# cnc-cape.net
KiCad netlist of a schematic drawn in EAGLE
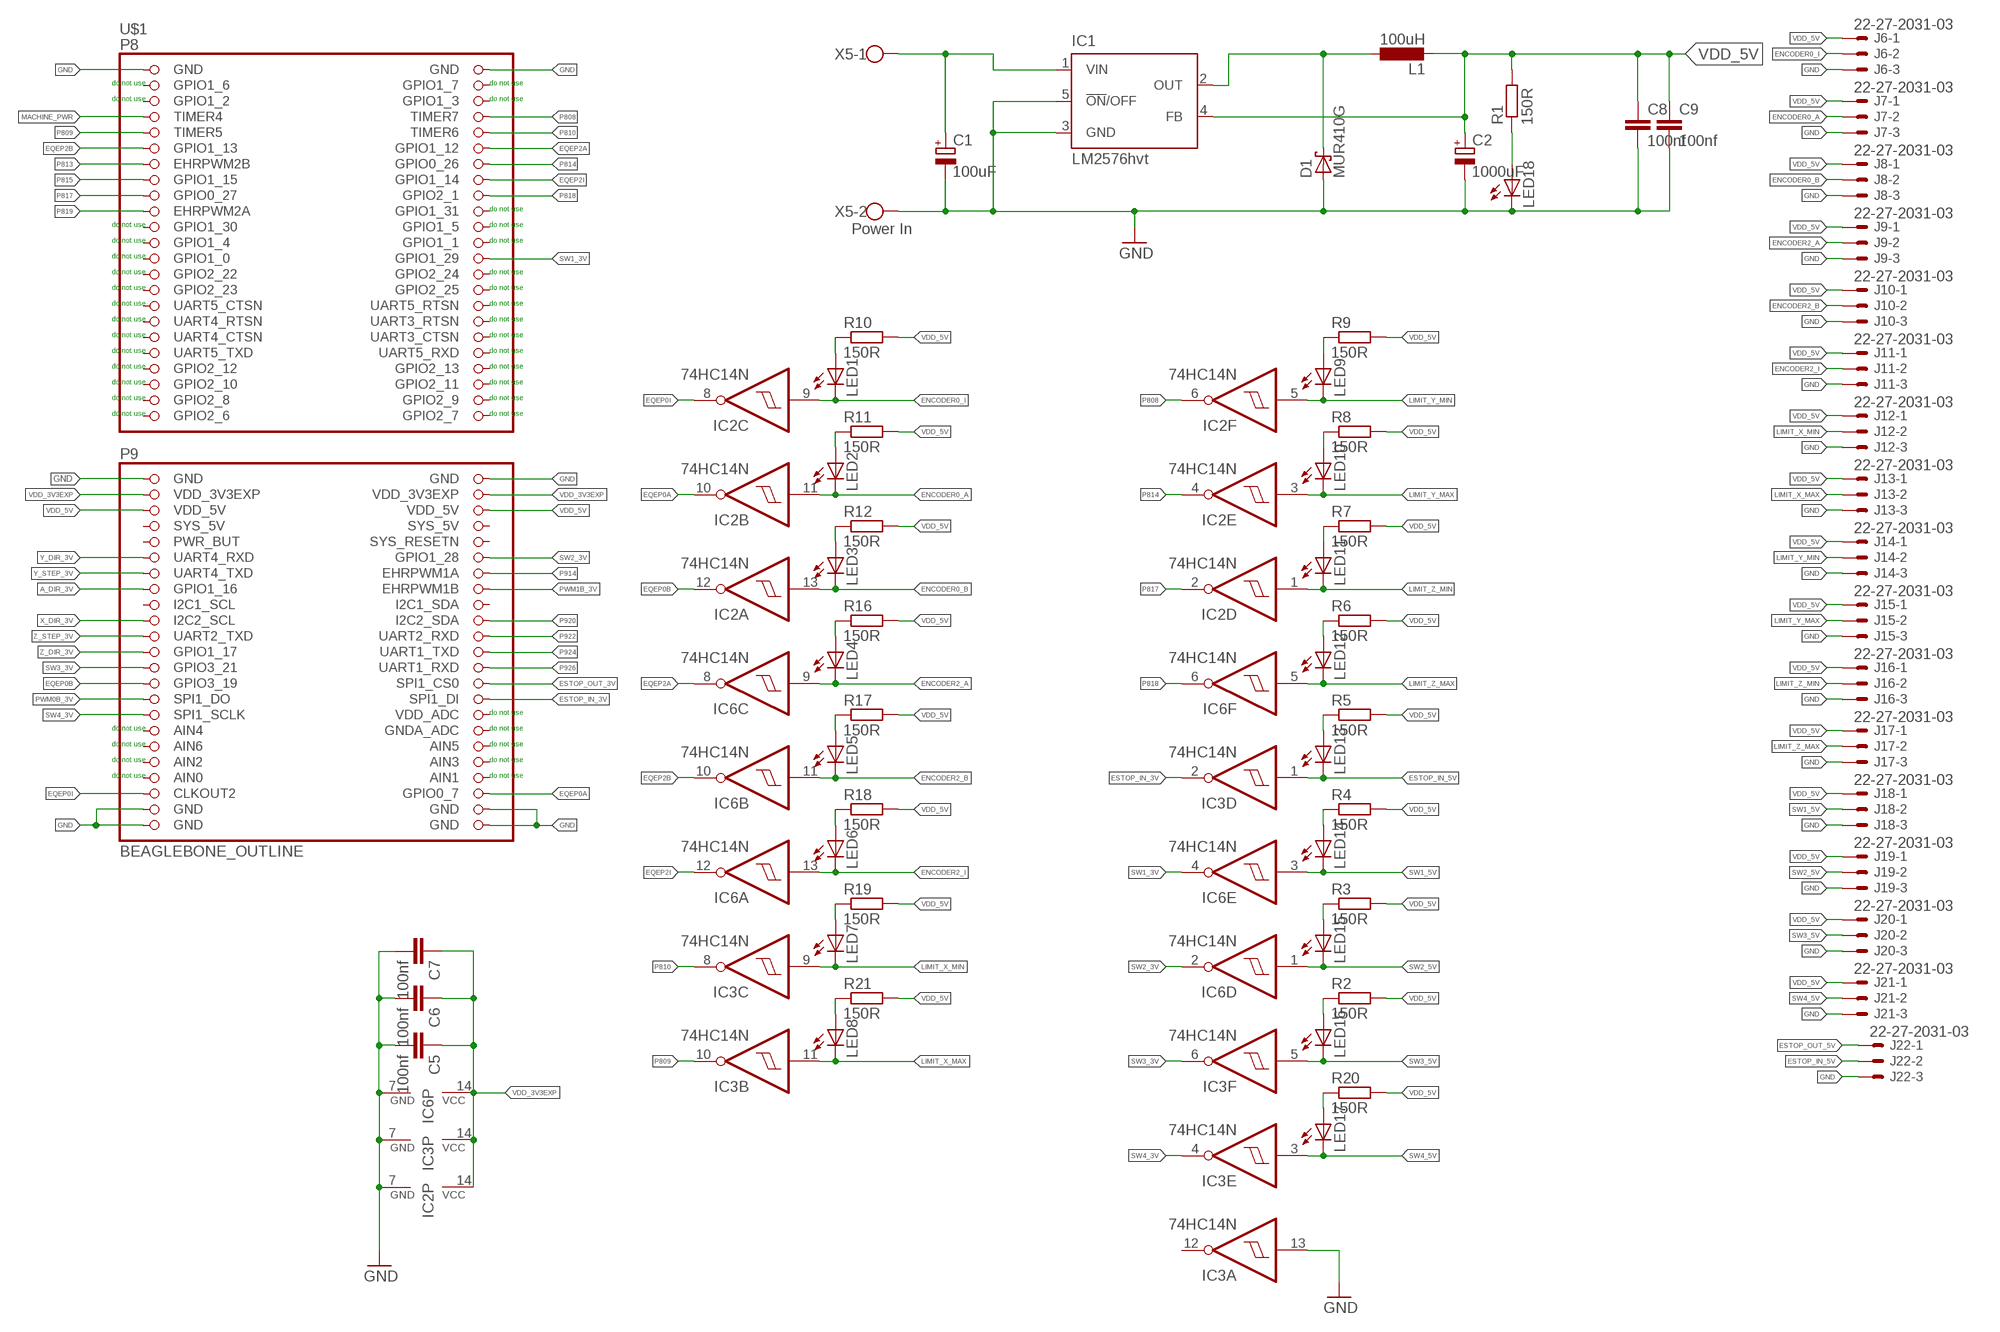
[diagram p0: schematic, sheet 1]
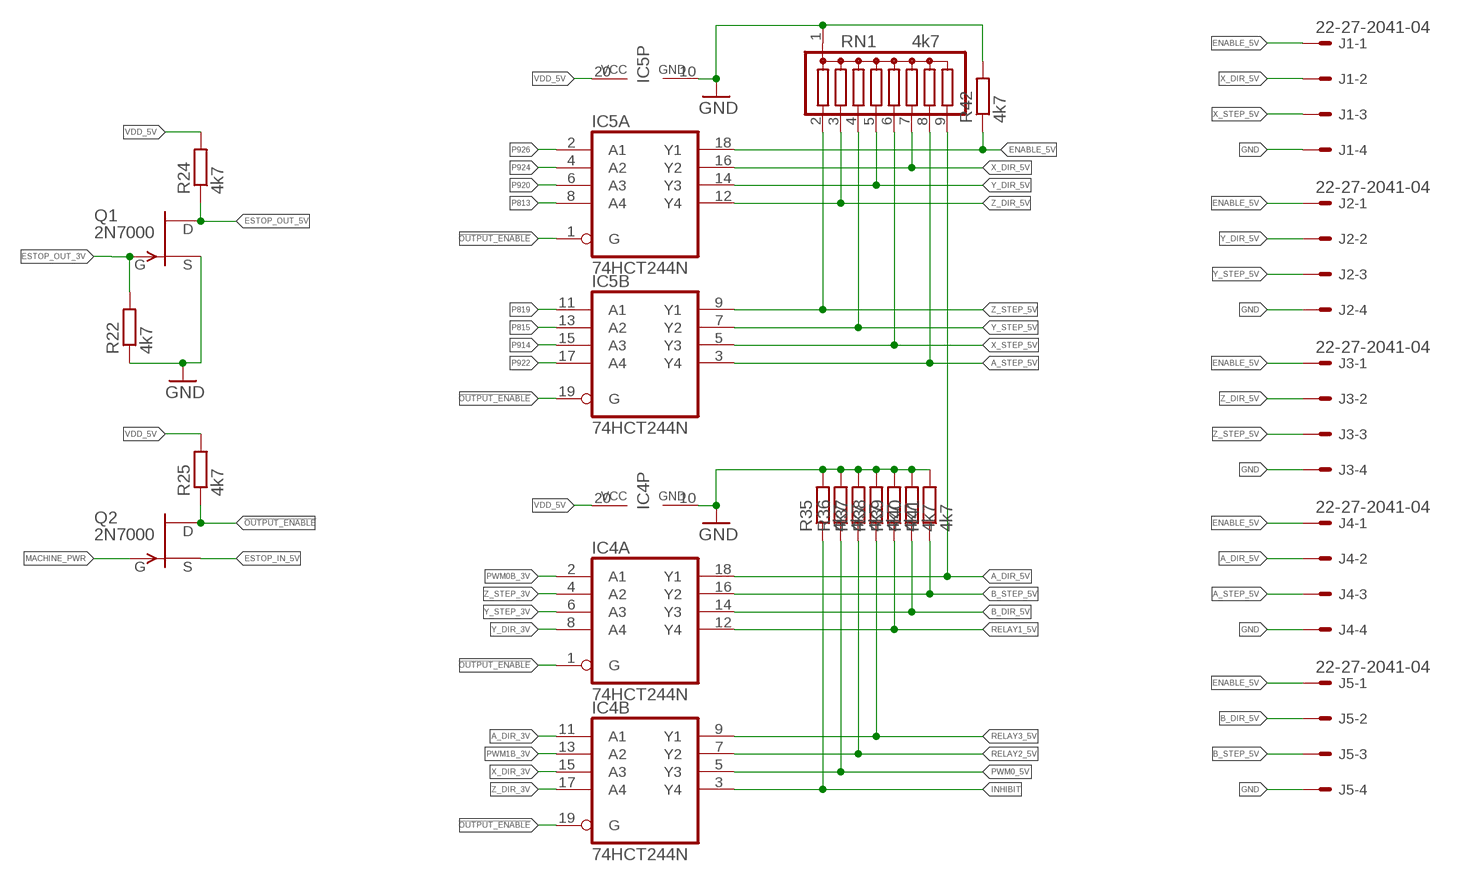
[diagram p1: schematic, sheet 2]
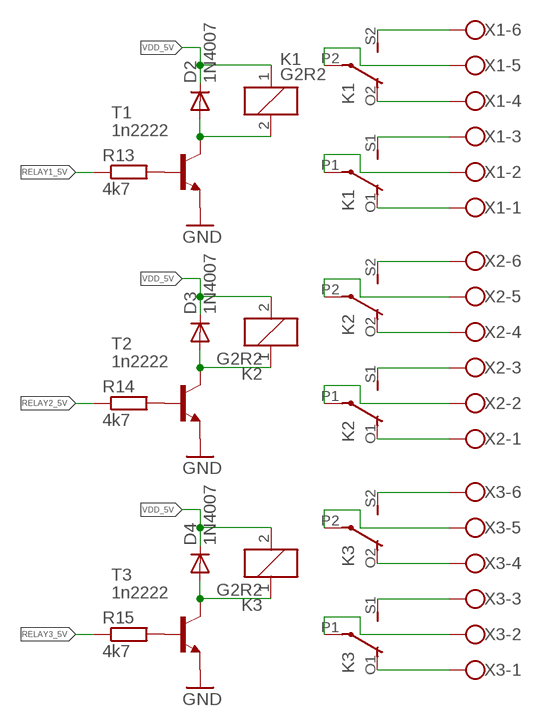
[diagram p2: schematic, sheet 3]
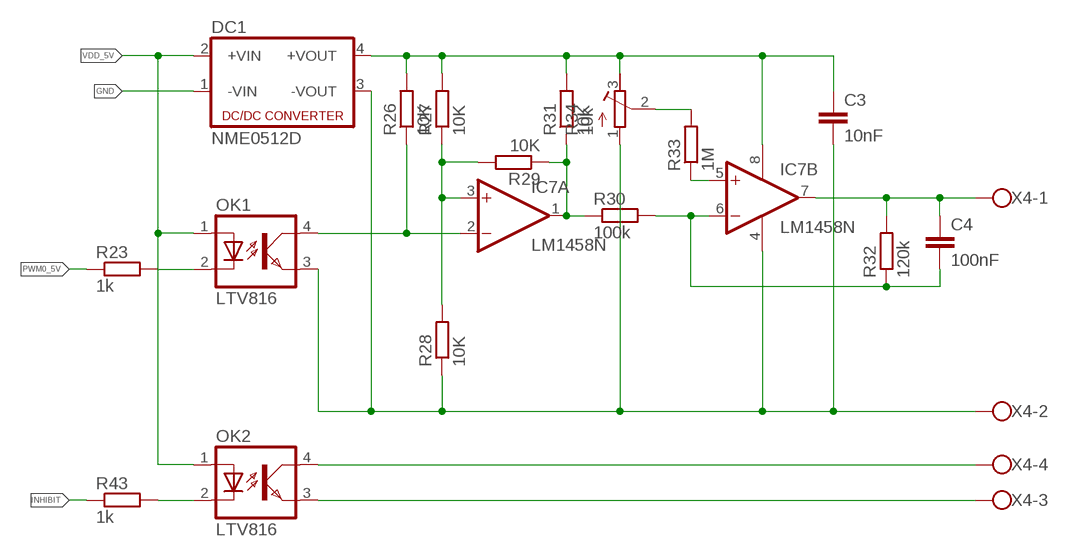
[diagram p3: schematic, sheet 4]

(export (version "E")
  (design (tool "Eeschema 10.0.6"))
  (components
    (comp (ref "IC4")
      (value "74HCT244N")
      (footprint "eagle-import:DIL20")
      (fields (field (name "FARNELL") "382267"))
      (libsource (lib "eagle-import") (part "74244NHCT"))
    )
    (comp (ref "IC5")
      (value "74HCT244N")
      (footprint "eagle-import:DIL20")
      (fields (field (name "FARNELL") "382267"))
      (libsource (lib "eagle-import") (part "74244NHCT"))
    )
    (comp (ref "J1")
      (value "22-27-2041-04")
      (footprint "eagle-import:6410-04")
      (fields (field (name "FARNELL") "9731164"))
      (libsource (lib "eagle-import") (part "22-?-0427-2041"))
    )
    (comp (ref "J2")
      (value "22-27-2041-04")
      (footprint "eagle-import:6410-04")
      (fields (field (name "FARNELL") "9731164"))
      (libsource (lib "eagle-import") (part "22-?-0427-2041"))
    )
    (comp (ref "J3")
      (value "22-27-2041-04")
      (footprint "eagle-import:6410-04")
      (fields (field (name "FARNELL") "9731164"))
      (libsource (lib "eagle-import") (part "22-?-0427-2041"))
    )
    (comp (ref "J4")
      (value "22-27-2041-04")
      (footprint "eagle-import:6410-04")
      (fields (field (name "FARNELL") "9731164"))
      (libsource (lib "eagle-import") (part "22-?-0427-2041"))
    )
    (comp (ref "J5")
      (value "22-27-2041-04")
      (footprint "eagle-import:6410-04")
      (fields (field (name "FARNELL") "9731164"))
      (libsource (lib "eagle-import") (part "22-?-0427-2041"))
    )
    (comp (ref "Q1")
      (value "2N7000")
      (footprint "eagle-import:TO92")
      (libsource (lib "eagle-import") (part "2N3819"))
    )
    (comp (ref "Q2")
      (value "2N7000")
      (footprint "eagle-import:TO92")
      (libsource (lib "eagle-import") (part "2N3819"))
    )
    (comp (ref "R22")
      (value "4k7")
      (footprint "eagle-import:0204_5")
      (libsource (lib "eagle-import") (part "R-EU_0204/5"))
    )
    (comp (ref "R24")
      (value "4k7")
      (footprint "eagle-import:0204_5")
      (libsource (lib "eagle-import") (part "R-EU_0204/5"))
    )
    (comp (ref "R25")
      (value "4k7")
      (footprint "eagle-import:0204_5")
      (libsource (lib "eagle-import") (part "R-EU_0204/5"))
    )
    (comp (ref "R35")
      (value "4k7")
      (footprint "eagle-import:0204_5")
      (libsource (lib "eagle-import") (part "R-EU_0204/5"))
    )
    (comp (ref "R36")
      (value "4k7")
      (footprint "eagle-import:0204_5")
      (libsource (lib "eagle-import") (part "R-EU_0204/5"))
    )
    (comp (ref "R37")
      (value "4k7")
      (footprint "eagle-import:0204_5")
      (libsource (lib "eagle-import") (part "R-EU_0204/5"))
    )
    (comp (ref "R38")
      (value "4k7")
      (footprint "eagle-import:0204_5")
      (libsource (lib "eagle-import") (part "R-EU_0204/5"))
    )
    (comp (ref "R39")
      (value "4k7")
      (footprint "eagle-import:0204_5")
      (libsource (lib "eagle-import") (part "R-EU_0204/5"))
    )
    (comp (ref "R40")
      (value "4k7")
      (footprint "eagle-import:0204_5")
      (libsource (lib "eagle-import") (part "R-EU_0204/5"))
    )
    (comp (ref "R41")
      (value "4k7")
      (footprint "eagle-import:0204_5")
      (libsource (lib "eagle-import") (part "R-EU_0204/5"))
    )
    (comp (ref "R42")
      (value "4k7")
      (footprint "eagle-import:0204_5")
      (libsource (lib "eagle-import") (part "R-EU_0204/5"))
    )
    (comp (ref "RN1")
      (value "4k7")
      (footprint "eagle-import:SIL9")
      (libsource (lib "eagle-import") (part "G08R"))
    )
    (comp (ref "C1")
      (value "100uF")
      (footprint "eagle-import:E5-10,5")
      (libsource (lib "eagle-import") (part "CPOL-EUE5-10.5"))
    )
    (comp (ref "C2")
      (value "1000uF")
      (footprint "eagle-import:E5-10,5")
      (libsource (lib "eagle-import") (part "CPOL-EUE5-10.5"))
    )
    (comp (ref "C5")
      (value "100nf")
      (footprint "eagle-import:C050-024X044")
      (libsource (lib "eagle-import") (part "C-EU050-024X044"))
    )
    (comp (ref "C6")
      (value "100nf")
      (footprint "eagle-import:C050-024X044")
      (libsource (lib "eagle-import") (part "C-EU050-024X044"))
    )
    (comp (ref "C7")
      (value "100nf")
      (footprint "eagle-import:C050-024X044")
      (libsource (lib "eagle-import") (part "C-EU050-024X044"))
    )
    (comp (ref "C8")
      (value "100nf")
      (footprint "eagle-import:C050-024X044")
      (libsource (lib "eagle-import") (part "C-EU050-024X044"))
    )
    (comp (ref "C9")
      (value "100nf")
      (footprint "eagle-import:C050-024X044")
      (libsource (lib "eagle-import") (part "C-EU050-024X044"))
    )
    (comp (ref "D1")
      (value "MUR410G")
      (footprint "eagle-import:DO201T15")
      (libsource (lib "eagle-import") (part "SCHOTTKY-DIODEDO201T15"))
    )
    (comp (ref "IC1")
      (value "LM2576hvt")
      (footprint "eagle-import:T05D")
      (fields (field (name "MPN") "LM2596T-ADJ/LF02"))
      (libsource (lib "eagle-import") (part "LM2596T"))
    )
    (comp (ref "IC2")
      (value "74HC14N")
      (footprint "eagle-import:DIL14")
      (fields (field (name "FARNELL") "1739974"))
      (libsource (lib "eagle-import") (part "7414NHC"))
    )
    (comp (ref "IC3")
      (value "74HC14N")
      (footprint "eagle-import:DIL14")
      (fields (field (name "FARNELL") "1739974"))
      (libsource (lib "eagle-import") (part "7414NHC"))
    )
    (comp (ref "IC6")
      (value "74HC14N")
      (footprint "eagle-import:DIL14")
      (fields (field (name "FARNELL") "1739974"))
      (libsource (lib "eagle-import") (part "7414NHC"))
    )
    (comp (ref "J6")
      (value "22-27-2031-03")
      (footprint "eagle-import:6410-03")
      (fields (field (name "FARNELL") "9731156"))
      (libsource (lib "eagle-import") (part "22-?-0327-2031"))
    )
    (comp (ref "J7")
      (value "22-27-2031-03")
      (footprint "eagle-import:6410-03")
      (fields (field (name "FARNELL") "9731156"))
      (libsource (lib "eagle-import") (part "22-?-0327-2031"))
    )
    (comp (ref "J8")
      (value "22-27-2031-03")
      (footprint "eagle-import:6410-03")
      (fields (field (name "FARNELL") "9731156"))
      (libsource (lib "eagle-import") (part "22-?-0327-2031"))
    )
    (comp (ref "J9")
      (value "22-27-2031-03")
      (footprint "eagle-import:6410-03")
      (libsource (lib "eagle-import") (part "22-?-0327-2031"))
    )
    (comp (ref "J10")
      (value "22-27-2031-03")
      (footprint "eagle-import:6410-03")
      (fields (field (name "FARNELL") "9731156"))
      (libsource (lib "eagle-import") (part "22-?-0327-2031"))
    )
    (comp (ref "J11")
      (value "22-27-2031-03")
      (footprint "eagle-import:6410-03")
      (fields (field (name "FARNELL") "9731156"))
      (libsource (lib "eagle-import") (part "22-?-0327-2031"))
    )
    (comp (ref "J12")
      (value "22-27-2031-03")
      (footprint "eagle-import:6410-03")
      (fields (field (name "FARNELL") "9731156"))
      (libsource (lib "eagle-import") (part "22-?-0327-2031"))
    )
    (comp (ref "J13")
      (value "22-27-2031-03")
      (footprint "eagle-import:6410-03")
      (fields (field (name "FARNELL") "9731156"))
      (libsource (lib "eagle-import") (part "22-?-0327-2031"))
    )
    (comp (ref "J14")
      (value "22-27-2031-03")
      (footprint "eagle-import:6410-03")
      (fields (field (name "FARNELL") "9731156"))
      (libsource (lib "eagle-import") (part "22-?-0327-2031"))
    )
    (comp (ref "J15")
      (value "22-27-2031-03")
      (footprint "eagle-import:6410-03")
      (fields (field (name "FARNELL") "9731156"))
      (libsource (lib "eagle-import") (part "22-?-0327-2031"))
    )
    (comp (ref "J16")
      (value "22-27-2031-03")
      (footprint "eagle-import:6410-03")
      (fields (field (name "FARNELL") "9731156"))
      (libsource (lib "eagle-import") (part "22-?-0327-2031"))
    )
    (comp (ref "J17")
      (value "22-27-2031-03")
      (footprint "eagle-import:6410-03")
      (fields (field (name "FARNELL") "9731156"))
      (libsource (lib "eagle-import") (part "22-?-0327-2031"))
    )
    (comp (ref "J18")
      (value "22-27-2031-03")
      (footprint "eagle-import:6410-03")
      (fields (field (name "FARNELL") "9731156"))
      (libsource (lib "eagle-import") (part "22-?-0327-2031"))
    )
    (comp (ref "J19")
      (value "22-27-2031-03")
      (footprint "eagle-import:6410-03")
      (fields (field (name "FARNELL") "9731156"))
      (libsource (lib "eagle-import") (part "22-?-0327-2031"))
    )
    (comp (ref "J20")
      (value "22-27-2031-03")
      (footprint "eagle-import:6410-03")
      (fields (field (name "FARNELL") "9731156"))
      (libsource (lib "eagle-import") (part "22-?-0327-2031"))
    )
    (comp (ref "J21")
      (value "22-27-2031-03")
      (footprint "eagle-import:6410-03")
      (fields (field (name "FARNELL") "9731156"))
      (libsource (lib "eagle-import") (part "22-?-0327-2031"))
    )
    (comp (ref "J22")
      (value "22-27-2031-03")
      (footprint "eagle-import:6410-03")
      (libsource (lib "eagle-import") (part "22-?-0327-2031"))
    )
    (comp (ref "L1")
      (value "100uH")
      (footprint "eagle-import:KM-4.0")
      (libsource (lib "eagle-import") (part "L-EU"))
    )
    (comp (ref "LED1")
      (value "LED3MM")
      (footprint "eagle-import:LED3MM")
      (libsource (lib "eagle-import") (part "LED3MM"))
    )
    (comp (ref "LED2")
      (value "LED3MM")
      (footprint "eagle-import:LED3MM")
      (libsource (lib "eagle-import") (part "LED3MM"))
    )
    (comp (ref "LED3")
      (value "LED3MM")
      (footprint "eagle-import:LED3MM")
      (libsource (lib "eagle-import") (part "LED3MM"))
    )
    (comp (ref "LED4")
      (value "LED3MM")
      (footprint "eagle-import:LED3MM")
      (libsource (lib "eagle-import") (part "LED3MM"))
    )
    (comp (ref "LED5")
      (value "LED3MM")
      (footprint "eagle-import:LED3MM")
      (libsource (lib "eagle-import") (part "LED3MM"))
    )
    (comp (ref "LED6")
      (value "LED3MM")
      (footprint "eagle-import:LED3MM")
      (libsource (lib "eagle-import") (part "LED3MM"))
    )
    (comp (ref "LED7")
      (value "LED3MM")
      (footprint "eagle-import:LED3MM")
      (libsource (lib "eagle-import") (part "LED3MM"))
    )
    (comp (ref "LED8")
      (value "LED3MM")
      (footprint "eagle-import:LED3MM")
      (libsource (lib "eagle-import") (part "LED3MM"))
    )
    (comp (ref "LED9")
      (value "LED3MM")
      (footprint "eagle-import:LED3MM")
      (libsource (lib "eagle-import") (part "LED3MM"))
    )
    (comp (ref "LED10")
      (value "LED3MM")
      (footprint "eagle-import:LED3MM")
      (libsource (lib "eagle-import") (part "LED3MM"))
    )
    (comp (ref "LED11")
      (value "LED3MM")
      (footprint "eagle-import:LED3MM")
      (libsource (lib "eagle-import") (part "LED3MM"))
    )
    (comp (ref "LED12")
      (value "LED3MM")
      (footprint "eagle-import:LED3MM")
      (libsource (lib "eagle-import") (part "LED3MM"))
    )
    (comp (ref "LED13")
      (value "LED3MM")
      (footprint "eagle-import:LED3MM")
      (libsource (lib "eagle-import") (part "LED3MM"))
    )
    (comp (ref "LED14")
      (value "LED3MM")
      (footprint "eagle-import:LED3MM")
      (libsource (lib "eagle-import") (part "LED3MM"))
    )
    (comp (ref "LED15")
      (value "LED3MM")
      (footprint "eagle-import:LED3MM")
      (libsource (lib "eagle-import") (part "LED3MM"))
    )
    (comp (ref "LED16")
      (value "LED3MM")
      (footprint "eagle-import:LED3MM")
      (libsource (lib "eagle-import") (part "LED3MM"))
    )
    (comp (ref "LED17")
      (value "LED3MM")
      (footprint "eagle-import:LED3MM")
      (libsource (lib "eagle-import") (part "LED3MM"))
    )
    (comp (ref "LED18")
      (value "LED3MM")
      (footprint "eagle-import:LED3MM")
      (libsource (lib "eagle-import") (part "LED3MM"))
    )
    (comp (ref "R1")
      (value "150R")
      (footprint "eagle-import:0204_5")
      (libsource (lib "eagle-import") (part "resistor_R-EU_0204/5"))
    )
    (comp (ref "R2")
      (value "150R")
      (footprint "eagle-import:0204_5")
      (libsource (lib "eagle-import") (part "resistor_R-EU_0204/5"))
    )
    (comp (ref "R3")
      (value "150R")
      (footprint "eagle-import:0204_5")
      (libsource (lib "eagle-import") (part "resistor_R-EU_0204/5"))
    )
    (comp (ref "R4")
      (value "150R")
      (footprint "eagle-import:0204_5")
      (libsource (lib "eagle-import") (part "resistor_R-EU_0204/5"))
    )
    (comp (ref "R5")
      (value "150R")
      (footprint "eagle-import:0204_5")
      (libsource (lib "eagle-import") (part "resistor_R-EU_0204/5"))
    )
    (comp (ref "R6")
      (value "150R")
      (footprint "eagle-import:0204_5")
      (libsource (lib "eagle-import") (part "resistor_R-EU_0204/5"))
    )
    (comp (ref "R7")
      (value "150R")
      (footprint "eagle-import:0204_5")
      (libsource (lib "eagle-import") (part "resistor_R-EU_0204/5"))
    )
    (comp (ref "R8")
      (value "150R")
      (footprint "eagle-import:0204_5")
      (libsource (lib "eagle-import") (part "resistor_R-EU_0204/5"))
    )
    (comp (ref "R9")
      (value "150R")
      (footprint "eagle-import:0204_5")
      (libsource (lib "eagle-import") (part "resistor_R-EU_0204/5"))
    )
    (comp (ref "R10")
      (value "150R")
      (footprint "eagle-import:0204_5")
      (libsource (lib "eagle-import") (part "resistor_R-EU_0204/5"))
    )
    (comp (ref "R11")
      (value "150R")
      (footprint "eagle-import:0204_5")
      (libsource (lib "eagle-import") (part "resistor_R-EU_0204/5"))
    )
    (comp (ref "R12")
      (value "150R")
      (footprint "eagle-import:0204_5")
      (libsource (lib "eagle-import") (part "resistor_R-EU_0204/5"))
    )
    (comp (ref "R16")
      (value "150R")
      (footprint "eagle-import:0204_5")
      (libsource (lib "eagle-import") (part "resistor_R-EU_0204/5"))
    )
    (comp (ref "R17")
      (value "150R")
      (footprint "eagle-import:0204_5")
      (libsource (lib "eagle-import") (part "resistor_R-EU_0204/5"))
    )
    (comp (ref "R18")
      (value "150R")
      (footprint "eagle-import:0204_5")
      (libsource (lib "eagle-import") (part "resistor_R-EU_0204/5"))
    )
    (comp (ref "R19")
      (value "150R")
      (footprint "eagle-import:0204_5")
      (libsource (lib "eagle-import") (part "resistor_R-EU_0204/5"))
    )
    (comp (ref "R20")
      (value "150R")
      (footprint "eagle-import:0204_5")
      (libsource (lib "eagle-import") (part "resistor_R-EU_0204/5"))
    )
    (comp (ref "R21")
      (value "150R")
      (footprint "eagle-import:0204_5")
      (libsource (lib "eagle-import") (part "resistor_R-EU_0204/5"))
    )
    (comp (ref "U$1")
      (value "BEAGLEBONE_OUTLINE")
      (footprint "eagle-import:BEAGLEBONE_SHIELD")
      (libsource (lib "eagle-import") (part "BEAGLEBONE_OUTLINE"))
    )
    (comp (ref "X5")
      (value "Power In")
      (footprint "eagle-import:W237-102")
      (fields (field (name "MPN") "237-102") (field (name "FARNELL") "3089034"))
      (libsource (lib "eagle-import") (part "W237-102"))
    )
    (comp (ref "C3")
      (value "10nF")
      (footprint "eagle-import:C050-024X044")
      (libsource (lib "eagle-import") (part "C-EU050-024X044"))
    )
    (comp (ref "C4")
      (value "100nF")
      (footprint "eagle-import:C050-024X044")
      (libsource (lib "eagle-import") (part "C-EU050-024X044"))
    )
    (comp (ref "DC1")
      (value "NME0512D")
      (footprint "eagle-import:NME")
      (fields (field (name "MF") "C & D TECHNOLOGIES, INC") (field (name "MPN") "NME1205D"))
      (libsource (lib "eagle-import") (part "NME"))
    )
    (comp (ref "IC7")
      (value "LM1458N")
      (footprint "eagle-import:DIL08")
      (libsource (lib "eagle-import") (part "1458NLM"))
    )
    (comp (ref "OK1")
      (value "LTV816")
      (footprint "eagle-import:DIL04")
      (libsource (lib "eagle-import") (part "LTV816"))
    )
    (comp (ref "OK2")
      (value "LTV816")
      (footprint "eagle-import:DIL04")
      (libsource (lib "eagle-import") (part "LTV816"))
    )
    (comp (ref "R23")
      (value "1k")
      (footprint "eagle-import:0204_5")
      (libsource (lib "eagle-import") (part "R-EU_0204/5"))
    )
    (comp (ref "R26")
      (value "10K")
      (footprint "eagle-import:0204_5")
      (libsource (lib "eagle-import") (part "R-EU_0204/5"))
    )
    (comp (ref "R27")
      (value "10K")
      (footprint "eagle-import:0204_5")
      (libsource (lib "eagle-import") (part "R-EU_0204/5"))
    )
    (comp (ref "R28")
      (value "10K")
      (footprint "eagle-import:0204_5")
      (libsource (lib "eagle-import") (part "R-EU_0204/5"))
    )
    (comp (ref "R29")
      (value "10K")
      (footprint "eagle-import:0204_5")
      (libsource (lib "eagle-import") (part "R-EU_0204/5"))
    )
    (comp (ref "R30")
      (value "100k")
      (footprint "eagle-import:0204_5")
      (libsource (lib "eagle-import") (part "R-EU_0204/5"))
    )
    (comp (ref "R31")
      (value "10K")
      (footprint "eagle-import:0204_5")
      (libsource (lib "eagle-import") (part "R-EU_0204/5"))
    )
    (comp (ref "R32")
      (value "120k")
      (footprint "eagle-import:0204_5")
      (libsource (lib "eagle-import") (part "R-EU_0204/5"))
    )
    (comp (ref "R33")
      (value "1M")
      (footprint "eagle-import:0204_5")
      (libsource (lib "eagle-import") (part "R-EU_0204/5"))
    )
    (comp (ref "R34")
      (value "10k")
      (footprint "eagle-import:RTRIM64P")
      (libsource (lib "eagle-import") (part "R-TRIMM64P"))
    )
    (comp (ref "R43")
      (value "1k")
      (footprint "eagle-import:0204_5")
      (libsource (lib "eagle-import") (part "R-EU_0204/5"))
    )
    (comp (ref "X4")
      (value "W237-4")
      (footprint "eagle-import:W237-4")
      (libsource (lib "eagle-import") (part "W237-4"))
    )
    (comp (ref "D2")
      (value "1N4007")
      (footprint "eagle-import:DO41-10")
      (libsource (lib "eagle-import") (part "1N4004"))
    )
    (comp (ref "D3")
      (value "1N4007")
      (footprint "eagle-import:DO41-10")
      (libsource (lib "eagle-import") (part "1N4004"))
    )
    (comp (ref "D4")
      (value "1N4007")
      (footprint "eagle-import:DO41-10")
      (libsource (lib "eagle-import") (part "1N4004"))
    )
    (comp (ref "K1")
      (value "G2R2")
      (footprint "eagle-import:G2R2")
      (fields
        (field (name "MF") "OMRON COMPONENTS USA")
        (field (name "MPN") "G2R-2-DC6")
        (field (name "FARNELL") "1703716")
      )
      (libsource (lib "eagle-import") (part "G2R2"))
    )
    (comp (ref "K2")
      (value "G2R2")
      (footprint "eagle-import:G2R2")
      (fields
        (field (name "MF") "OMRON COMPONENTS USA")
        (field (name "MPN") "G2R-2-DC6")
        (field (name "FARNELL") "1703716")
      )
      (libsource (lib "eagle-import") (part "G2R2"))
    )
    (comp (ref "K3")
      (value "G2R2")
      (footprint "eagle-import:G2R2")
      (fields
        (field (name "MF") "OMRON COMPONENTS USA")
        (field (name "MPN") "G2R-2-DC6")
        (field (name "FARNELL") "1703716")
      )
      (libsource (lib "eagle-import") (part "G2R2"))
    )
    (comp (ref "R13")
      (value "4k7")
      (footprint "eagle-import:0204_5")
      (libsource (lib "eagle-import") (part "R-EU_0204/5"))
    )
    (comp (ref "R14")
      (value "4k7")
      (footprint "eagle-import:0204_5")
      (libsource (lib "eagle-import") (part "R-EU_0204/5"))
    )
    (comp (ref "R15")
      (value "4k7")
      (footprint "eagle-import:0204_5")
      (libsource (lib "eagle-import") (part "R-EU_0204/5"))
    )
    (comp (ref "T1")
      (value "1n2222")
      (footprint "eagle-import:TO92")
      (libsource (lib "eagle-import") (part "-NPN-TO92"))
    )
    (comp (ref "T2")
      (value "1n2222")
      (footprint "eagle-import:TO92")
      (libsource (lib "eagle-import") (part "-NPN-TO92"))
    )
    (comp (ref "T3")
      (value "1n2222")
      (footprint "eagle-import:TO92")
      (libsource (lib "eagle-import") (part "-NPN-TO92"))
    )
    (comp (ref "X1")
      (value "W237-6")
      (footprint "eagle-import:W237-6")
      (fields (field (name "FARNELL") "3089071"))
      (libsource (lib "eagle-import") (part "W237-6"))
    )
    (comp (ref "X2")
      (value "W237-6")
      (footprint "eagle-import:W237-6")
      (fields (field (name "FARNELL") "3089071"))
      (libsource (lib "eagle-import") (part "W237-6"))
    )
    (comp (ref "X3")
      (value "W237-6")
      (footprint "eagle-import:W237-6")
      (fields (field (name "FARNELL") "3089071"))
      (libsource (lib "eagle-import") (part "W237-6"))
    )
  )
  (nets
    (net (code "1") (name "AIN0") (class "Default")
      (node (ref "U$1") (pin "85") (pinfunction "AIN0_85") (pintype "power_in"))
    )
    (net (code "2") (name "A_DIR_3V") (class "Default")
      (node (ref "IC4") (pin "11") (pinfunction "A1_11") (pintype "input"))
      (node (ref "U$1") (pin "61") (pinfunction "GPIO1_16_61") (pintype "passive"))
    )
    (net (code "3") (name "A_DIR_5V") (class "Default")
      (node (ref "IC4") (pin "18") (pinfunction "Y1_18") (pintype "tri_state"))
      (node (ref "J4") (pin "2") (pinfunction "S_2") (pintype "passive"))
      (node (ref "RN1") (pin "9") (pinfunction "9_9") (pintype "passive"))
    )
    (net (code "4") (name "A_STEP_5V") (class "Default")
      (node (ref "IC5") (pin "3") (pinfunction "Y4_3") (pintype "tri_state"))
      (node (ref "J4") (pin "3") (pinfunction "S_3") (pintype "passive"))
      (node (ref "RN1") (pin "8") (pinfunction "8_8") (pintype "passive"))
    )
    (net (code "5") (name "B_DIR_5V") (class "Default")
      (node (ref "IC4") (pin "14") (pinfunction "Y3_14") (pintype "tri_state"))
      (node (ref "J5") (pin "2") (pinfunction "S_2") (pintype "passive"))
      (node (ref "R40") (pin "1") (pinfunction "1_1") (pintype "passive"))
    )
    (net (code "6") (name "B_STEP_5V") (class "Default")
      (node (ref "IC4") (pin "16") (pinfunction "Y2_16") (pintype "tri_state"))
      (node (ref "J5") (pin "3") (pinfunction "S_3") (pintype "passive"))
      (node (ref "R41") (pin "1") (pinfunction "1_1") (pintype "passive"))
    )
    (net (code "7") (name "ENABLE_5V") (class "Default")
      (node (ref "IC5") (pin "18") (pinfunction "Y1_18") (pintype "tri_state"))
      (node (ref "J1") (pin "1") (pinfunction "S_1") (pintype "passive"))
      (node (ref "J2") (pin "1") (pinfunction "S_1") (pintype "passive"))
      (node (ref "J3") (pin "1") (pinfunction "S_1") (pintype "passive"))
      (node (ref "J4") (pin "1") (pinfunction "S_1") (pintype "passive"))
      (node (ref "J5") (pin "1") (pinfunction "S_1") (pintype "passive"))
      (node (ref "R42") (pin "1") (pinfunction "1_1") (pintype "passive"))
    )
    (net (code "8") (name "ENCODER0_A") (class "Default")
      (node (ref "IC2") (pin "11") (pinfunction "I_11") (pintype "input"))
      (node (ref "J7") (pin "2") (pinfunction "S_2") (pintype "passive"))
      (node (ref "LED2") (pin "K") (pinfunction "C_K") (pintype "passive"))
    )
    (net (code "9") (name "ENCODER0_B") (class "Default")
      (node (ref "IC2") (pin "13") (pinfunction "I_13") (pintype "input"))
      (node (ref "J8") (pin "2") (pinfunction "S_2") (pintype "passive"))
      (node (ref "LED3") (pin "K") (pinfunction "C_K") (pintype "passive"))
    )
    (net (code "10") (name "ENCODER0_I") (class "Default")
      (node (ref "IC2") (pin "9") (pinfunction "I_9") (pintype "input"))
      (node (ref "J6") (pin "2") (pinfunction "S_2") (pintype "passive"))
      (node (ref "LED1") (pin "K") (pinfunction "C_K") (pintype "passive"))
    )
    (net (code "11") (name "ENCODER2_A") (class "Default")
      (node (ref "IC6") (pin "9") (pinfunction "I_9") (pintype "input"))
      (node (ref "J9") (pin "2") (pinfunction "S_2") (pintype "passive"))
      (node (ref "LED4") (pin "K") (pinfunction "C_K") (pintype "passive"))
    )
    (net (code "12") (name "ENCODER2_B") (class "Default")
      (node (ref "IC6") (pin "11") (pinfunction "I_11") (pintype "input"))
      (node (ref "J10") (pin "2") (pinfunction "S_2") (pintype "passive"))
      (node (ref "LED5") (pin "K") (pinfunction "C_K") (pintype "passive"))
    )
    (net (code "13") (name "ENCODER2_I") (class "Default")
      (node (ref "IC6") (pin "13") (pinfunction "I_13") (pintype "input"))
      (node (ref "J11") (pin "2") (pinfunction "S_2") (pintype "passive"))
      (node (ref "LED6") (pin "K") (pinfunction "C_K") (pintype "passive"))
    )
    (net (code "14") (name "EQEP0A") (class "Default")
      (node (ref "IC2") (pin "10") (pinfunction "O_10") (pintype "output"))
      (node (ref "U$1") (pin "88") (pinfunction "GPIO0_7_88") (pintype "passive"))
    )
    (net (code "15") (name "EQEP0B") (class "Default")
      (node (ref "IC2") (pin "12") (pinfunction "O_12") (pintype "output"))
      (node (ref "U$1") (pin "73") (pinfunction "GPIO3_19_73") (pintype "passive"))
    )
    (net (code "16") (name "EQEP0I") (class "Default")
      (node (ref "IC2") (pin "8") (pinfunction "O_8") (pintype "output"))
      (node (ref "U$1") (pin "87") (pinfunction "CLKOUT2_87") (pintype "input"))
    )
    (net (code "17") (name "EQEP2A") (class "Default")
      (node (ref "IC6") (pin "8") (pinfunction "O_8") (pintype "output"))
      (node (ref "U$1") (pin "12") (pinfunction "GPIO1_12_12") (pintype "passive"))
    )
    (net (code "18") (name "EQEP2B") (class "Default")
      (node (ref "IC6") (pin "10") (pinfunction "O_10") (pintype "output"))
      (node (ref "U$1") (pin "11") (pinfunction "GPIO1_13_11") (pintype "passive"))
    )
    (net (code "19") (name "EQEP2I") (class "Default")
      (node (ref "IC6") (pin "12") (pinfunction "O_12") (pintype "output"))
      (node (ref "U$1") (pin "16") (pinfunction "GPIO1_14_16") (pintype "passive"))
    )
    (net (code "20") (name "ESTOP_IN_3V") (class "Default")
      (node (ref "IC3") (pin "2") (pinfunction "O_2") (pintype "output"))
      (node (ref "U$1") (pin "76") (pinfunction "SPI1_DI_76") (pintype "passive"))
    )
    (net (code "21") (name "ESTOP_IN_5V") (class "Default")
      (node (ref "IC3") (pin "1") (pinfunction "I_1") (pintype "input"))
      (node (ref "J22") (pin "2") (pinfunction "S_2") (pintype "passive"))
      (node (ref "LED13") (pin "K") (pinfunction "C_K") (pintype "passive"))
      (node (ref "Q2") (pin "3") (pinfunction "S_3") (pintype "passive"))
    )
    (net (code "22") (name "ESTOP_OUT_3V") (class "Default")
      (node (ref "Q1") (pin "2") (pinfunction "G_2") (pintype "passive"))
      (node (ref "R22") (pin "2") (pinfunction "2_2") (pintype "passive"))
      (node (ref "U$1") (pin "74") (pinfunction "SPI1_CS0_74") (pintype "passive"))
    )
    (net (code "23") (name "ESTOP_OUT_5V") (class "Default")
      (node (ref "J22") (pin "1") (pinfunction "S_1") (pintype "passive"))
      (node (ref "Q1") (pin "1") (pinfunction "D_1") (pintype "passive"))
      (node (ref "R24") (pin "1") (pinfunction "1_1") (pintype "passive"))
    )
    (net (code "24") (name "GND") (class "Default")
      (node (ref "C1") (pin "-") (pinfunction "-_-") (pintype "passive"))
      (node (ref "C2") (pin "-") (pinfunction "-_-") (pintype "passive"))
      (node (ref "C5") (pin "2") (pinfunction "2_2") (pintype "passive"))
      (node (ref "C6") (pin "2") (pinfunction "2_2") (pintype "passive"))
      (node (ref "C7") (pin "2") (pinfunction "2_2") (pintype "passive"))
      (node (ref "C8") (pin "2") (pinfunction "2_2") (pintype "passive"))
      (node (ref "C9") (pin "2") (pinfunction "2_2") (pintype "passive"))
      (node (ref "D1") (pin "A") (pinfunction "A_A") (pintype "passive"))
      (node (ref "DC1") (pin "1") (pinfunction "-VIN_1") (pintype "passive"))
      (node (ref "IC1") (pin "3") (pinfunction "GND_3") (pintype "power_in"))
      (node (ref "IC1") (pin "5") (pinfunction "~{ON}/OFF_5") (pintype "input"))
      (node (ref "IC2") (pin "7") (pinfunction "GND_7") (pintype "power_in"))
      (node (ref "IC3") (pin "13") (pinfunction "I_13") (pintype "input"))
      (node (ref "IC3") (pin "7") (pinfunction "GND_7") (pintype "power_in"))
      (node (ref "IC4") (pin "10") (pinfunction "GND_10") (pintype "power_in"))
      (node (ref "IC5") (pin "10") (pinfunction "GND_10") (pintype "power_in"))
      (node (ref "IC6") (pin "7") (pinfunction "GND_7") (pintype "power_in"))
      (node (ref "J1") (pin "4") (pinfunction "S_4") (pintype "passive"))
      (node (ref "J10") (pin "3") (pinfunction "S_3") (pintype "passive"))
      (node (ref "J11") (pin "3") (pinfunction "S_3") (pintype "passive"))
      (node (ref "J12") (pin "3") (pinfunction "S_3") (pintype "passive"))
      (node (ref "J13") (pin "3") (pinfunction "S_3") (pintype "passive"))
      (node (ref "J14") (pin "3") (pinfunction "S_3") (pintype "passive"))
      (node (ref "J15") (pin "3") (pinfunction "S_3") (pintype "passive"))
      (node (ref "J16") (pin "3") (pinfunction "S_3") (pintype "passive"))
      (node (ref "J17") (pin "3") (pinfunction "S_3") (pintype "passive"))
      (node (ref "J18") (pin "3") (pinfunction "S_3") (pintype "passive"))
      (node (ref "J19") (pin "3") (pinfunction "S_3") (pintype "passive"))
      (node (ref "J2") (pin "4") (pinfunction "S_4") (pintype "passive"))
      (node (ref "J20") (pin "3") (pinfunction "S_3") (pintype "passive"))
      (node (ref "J21") (pin "3") (pinfunction "S_3") (pintype "passive"))
      (node (ref "J22") (pin "3") (pinfunction "S_3") (pintype "passive"))
      (node (ref "J3") (pin "4") (pinfunction "S_4") (pintype "passive"))
      (node (ref "J4") (pin "4") (pinfunction "S_4") (pintype "passive"))
      (node (ref "J5") (pin "4") (pinfunction "S_4") (pintype "passive"))
      (node (ref "J6") (pin "3") (pinfunction "S_3") (pintype "passive"))
      (node (ref "J7") (pin "3") (pinfunction "S_3") (pintype "passive"))
      (node (ref "J8") (pin "3") (pinfunction "S_3") (pintype "passive"))
      (node (ref "J9") (pin "3") (pinfunction "S_3") (pintype "passive"))
      (node (ref "LED18") (pin "K") (pinfunction "C_K") (pintype "passive"))
      (node (ref "Q1") (pin "3") (pinfunction "S_3") (pintype "passive"))
      (node (ref "R22") (pin "1") (pinfunction "1_1") (pintype "passive"))
      (node (ref "R35") (pin "2") (pinfunction "2_2") (pintype "passive"))
      (node (ref "R36") (pin "2") (pinfunction "2_2") (pintype "passive"))
      (node (ref "R37") (pin "2") (pinfunction "2_2") (pintype "passive"))
      (node (ref "R38") (pin "2") (pinfunction "2_2") (pintype "passive"))
      (node (ref "R39") (pin "2") (pinfunction "2_2") (pintype "passive"))
      (node (ref "R40") (pin "2") (pinfunction "2_2") (pintype "passive"))
      (node (ref "R41") (pin "2") (pinfunction "2_2") (pintype "passive"))
      (node (ref "R42") (pin "2") (pinfunction "2_2") (pintype "passive"))
      (node (ref "RN1") (pin "1") (pinfunction "1_1") (pintype "passive"))
      (node (ref "T1") (pin "1") (pinfunction "E_1") (pintype "passive"))
      (node (ref "T2") (pin "1") (pinfunction "E_1") (pintype "passive"))
      (node (ref "T3") (pin "1") (pinfunction "E_1") (pintype "passive"))
      (node (ref "U$1") (pin "1") (pinfunction "GND_1") (pintype "power_in"))
      (node (ref "U$1") (pin "2") (pinfunction "GND_2") (pintype "power_in"))
      (node (ref "U$1") (pin "47") (pinfunction "GND_47") (pintype "power_in"))
      (node (ref "U$1") (pin "48") (pinfunction "GND_48") (pintype "power_in"))
      (node (ref "U$1") (pin "89") (pinfunction "GND_89") (pintype "power_in"))
      (node (ref "U$1") (pin "90") (pinfunction "GND_90") (pintype "power_in"))
      (node (ref "U$1") (pin "91") (pinfunction "GND_91") (pintype "power_in"))
      (node (ref "U$1") (pin "92") (pinfunction "GND_92") (pintype "power_in"))
      (node (ref "X5") (pin "2") (pinfunction "KL_2") (pintype "passive"))
    )
    (net (code "25") (name "INHIBIT") (class "Default")
      (node (ref "IC4") (pin "3") (pinfunction "Y4_3") (pintype "tri_state"))
      (node (ref "R35") (pin "1") (pinfunction "1_1") (pintype "passive"))
      (node (ref "R43") (pin "1") (pinfunction "1_1") (pintype "passive"))
    )
    (net (code "26") (name "LIMIT_X_MAX") (class "Default")
      (node (ref "IC3") (pin "11") (pinfunction "I_11") (pintype "input"))
      (node (ref "J13") (pin "2") (pinfunction "S_2") (pintype "passive"))
      (node (ref "LED8") (pin "K") (pinfunction "C_K") (pintype "passive"))
    )
    (net (code "27") (name "LIMIT_X_MIN") (class "Default")
      (node (ref "IC3") (pin "9") (pinfunction "I_9") (pintype "input"))
      (node (ref "J12") (pin "2") (pinfunction "S_2") (pintype "passive"))
      (node (ref "LED7") (pin "K") (pinfunction "C_K") (pintype "passive"))
    )
    (net (code "28") (name "LIMIT_Y_MAX") (class "Default")
      (node (ref "IC2") (pin "3") (pinfunction "I_3") (pintype "input"))
      (node (ref "J15") (pin "2") (pinfunction "S_2") (pintype "passive"))
      (node (ref "LED10") (pin "K") (pinfunction "C_K") (pintype "passive"))
    )
    (net (code "29") (name "LIMIT_Y_MIN") (class "Default")
      (node (ref "IC2") (pin "5") (pinfunction "I_5") (pintype "input"))
      (node (ref "J14") (pin "2") (pinfunction "S_2") (pintype "passive"))
      (node (ref "LED9") (pin "K") (pinfunction "C_K") (pintype "passive"))
    )
    (net (code "30") (name "LIMIT_Z_MAX") (class "Default")
      (node (ref "IC6") (pin "5") (pinfunction "I_5") (pintype "input"))
      (node (ref "J17") (pin "2") (pinfunction "S_2") (pintype "passive"))
      (node (ref "LED12") (pin "K") (pinfunction "C_K") (pintype "passive"))
    )
    (net (code "31") (name "LIMIT_Z_MIN") (class "Default")
      (node (ref "IC2") (pin "1") (pinfunction "I_1") (pintype "input"))
      (node (ref "J16") (pin "2") (pinfunction "S_2") (pintype "passive"))
      (node (ref "LED11") (pin "K") (pinfunction "C_K") (pintype "passive"))
    )
    (net (code "32") (name "MACHINE_PWR") (class "Default")
      (node (ref "Q2") (pin "2") (pinfunction "G_2") (pintype "passive"))
      (node (ref "U$1") (pin "7") (pinfunction "TIMER4_7") (pintype "passive"))
    )
    (net (code "33") (name "Net-(DC1-+VOUT)") (class "Default")
      (node (ref "C3") (pin "1") (pinfunction "1_1") (pintype "passive"))
      (node (ref "DC1") (pin "4") (pinfunction "+VOUT_4") (pintype "passive"))
      (node (ref "IC7") (pin "8") (pinfunction "V+_8") (pintype "power_in"))
      (node (ref "R26") (pin "2") (pinfunction "2_2") (pintype "passive"))
      (node (ref "R27") (pin "2") (pinfunction "2_2") (pintype "passive"))
      (node (ref "R31") (pin "2") (pinfunction "2_2") (pintype "passive"))
      (node (ref "R34") (pin "3") (pinfunction "E_3") (pintype "passive"))
    )
    (net (code "34") (name "Net-(DC1--VOUT)") (class "Default")
      (node (ref "C3") (pin "2") (pinfunction "2_2") (pintype "passive"))
      (node (ref "DC1") (pin "3") (pinfunction "-VOUT_3") (pintype "passive"))
      (node (ref "IC7") (pin "4") (pinfunction "V-_4") (pintype "power_in"))
      (node (ref "OK1") (pin "3") (pinfunction "EMIT_3") (pintype "passive"))
      (node (ref "R28") (pin "1") (pinfunction "1_1") (pintype "passive"))
      (node (ref "R34") (pin "1") (pinfunction "A_1") (pintype "passive"))
      (node (ref "X4") (pin "2") (pinfunction "KL_2") (pintype "passive"))
    )
    (net (code "35") (name "Net-(IC1-OUT)") (class "Default")
      (node (ref "D1") (pin "C") (pinfunction "C_C") (pintype "passive"))
      (node (ref "IC1") (pin "2") (pinfunction "OUT_2") (pintype "output"))
      (node (ref "L1") (pin "P$1") (pinfunction "1_P$1") (pintype "passive"))
    )
    (net (code "36") (name "Net-(IC1-VIN)") (class "Default")
      (node (ref "C1") (pin "+") (pinfunction "+_+") (pintype "passive"))
      (node (ref "IC1") (pin "1") (pinfunction "VIN_1") (pintype "input"))
      (node (ref "X5") (pin "1") (pinfunction "KL_1") (pintype "passive"))
    )
    (net (code "37") (name "Net-(IC7A-+IN)") (class "Default")
      (node (ref "IC7") (pin "3") (pinfunction "+IN_3") (pintype "input"))
      (node (ref "R27") (pin "1") (pinfunction "1_1") (pintype "passive"))
      (node (ref "R28") (pin "2") (pinfunction "2_2") (pintype "passive"))
      (node (ref "R29") (pin "2") (pinfunction "2_2") (pintype "passive"))
    )
    (net (code "38") (name "Net-(IC7A--IN)") (class "Default")
      (node (ref "IC7") (pin "2") (pinfunction "-IN_2") (pintype "input"))
      (node (ref "OK1") (pin "4") (pinfunction "COL_4") (pintype "passive"))
      (node (ref "R26") (pin "1") (pinfunction "1_1") (pintype "passive"))
    )
    (net (code "39") (name "Net-(IC7A-OUT)") (class "Default")
      (node (ref "IC7") (pin "1") (pinfunction "OUT_1") (pintype "output"))
      (node (ref "R29") (pin "1") (pinfunction "1_1") (pintype "passive"))
      (node (ref "R30") (pin "1") (pinfunction "1_1") (pintype "passive"))
      (node (ref "R31") (pin "1") (pinfunction "1_1") (pintype "passive"))
    )
    (net (code "40") (name "Net-(IC7B-+IN)") (class "Default")
      (node (ref "IC7") (pin "5") (pinfunction "+IN_5") (pintype "input"))
      (node (ref "R33") (pin "1") (pinfunction "1_1") (pintype "passive"))
    )
    (net (code "41") (name "Net-(IC7B--IN)") (class "Default")
      (node (ref "C4") (pin "2") (pinfunction "2_2") (pintype "passive"))
      (node (ref "IC7") (pin "6") (pinfunction "-IN_6") (pintype "input"))
      (node (ref "R30") (pin "2") (pinfunction "2_2") (pintype "passive"))
      (node (ref "R32") (pin "1") (pinfunction "1_1") (pintype "passive"))
    )
    (net (code "42") (name "Net-(IC7B-OUT)") (class "Default")
      (node (ref "C4") (pin "1") (pinfunction "1_1") (pintype "passive"))
      (node (ref "IC7") (pin "7") (pinfunction "OUT_7") (pintype "output"))
      (node (ref "R32") (pin "2") (pinfunction "2_2") (pintype "passive"))
      (node (ref "X4") (pin "1") (pinfunction "KL_1") (pintype "passive"))
    )
    (net (code "43") (name "Net-(K1B-O)") (class "Default")
      (node (ref "K1") (pin "O1") (pinfunction "O_O1") (pintype "passive"))
      (node (ref "X1") (pin "1") (pinfunction "KL_1") (pintype "passive"))
    )
    (net (code "44") (name "Net-(K1B-P)") (class "Default")
      (node (ref "K1") (pin "P1") (pinfunction "P_P1") (pintype "passive"))
      (node (ref "X1") (pin "2") (pinfunction "KL_2") (pintype "passive"))
    )
    (net (code "45") (name "Net-(K1B-S)") (class "Default")
      (node (ref "K1") (pin "S1") (pinfunction "S_S1") (pintype "passive"))
      (node (ref "X1") (pin "3") (pinfunction "KL_3") (pintype "passive"))
    )
    (net (code "46") (name "Net-(K1C-O)") (class "Default")
      (node (ref "K1") (pin "O2") (pinfunction "O_O2") (pintype "passive"))
      (node (ref "X1") (pin "4") (pinfunction "KL_4") (pintype "passive"))
    )
    (net (code "47") (name "Net-(K1C-P)") (class "Default")
      (node (ref "K1") (pin "P2") (pinfunction "P_P2") (pintype "passive"))
      (node (ref "X1") (pin "5") (pinfunction "KL_5") (pintype "passive"))
    )
    (net (code "48") (name "Net-(K1C-S)") (class "Default")
      (node (ref "K1") (pin "S2") (pinfunction "S_S2") (pintype "passive"))
      (node (ref "X1") (pin "6") (pinfunction "KL_6") (pintype "passive"))
    )
    (net (code "49") (name "Net-(K2B-O)") (class "Default")
      (node (ref "K2") (pin "O1") (pinfunction "O_O1") (pintype "passive"))
      (node (ref "X2") (pin "1") (pinfunction "KL_1") (pintype "passive"))
    )
    (net (code "50") (name "Net-(K2B-P)") (class "Default")
      (node (ref "K2") (pin "P1") (pinfunction "P_P1") (pintype "passive"))
      (node (ref "X2") (pin "2") (pinfunction "KL_2") (pintype "passive"))
    )
    (net (code "51") (name "Net-(K2B-S)") (class "Default")
      (node (ref "K2") (pin "S1") (pinfunction "S_S1") (pintype "passive"))
      (node (ref "X2") (pin "3") (pinfunction "KL_3") (pintype "passive"))
    )
    (net (code "52") (name "Net-(K2C-O)") (class "Default")
      (node (ref "K2") (pin "O2") (pinfunction "O_O2") (pintype "passive"))
      (node (ref "X2") (pin "4") (pinfunction "KL_4") (pintype "passive"))
    )
    (net (code "53") (name "Net-(K2C-P)") (class "Default")
      (node (ref "K2") (pin "P2") (pinfunction "P_P2") (pintype "passive"))
      (node (ref "X2") (pin "5") (pinfunction "KL_5") (pintype "passive"))
    )
    (net (code "54") (name "Net-(K2C-S)") (class "Default")
      (node (ref "K2") (pin "S2") (pinfunction "S_S2") (pintype "passive"))
      (node (ref "X2") (pin "6") (pinfunction "KL_6") (pintype "passive"))
    )
    (net (code "55") (name "Net-(K3B-O)") (class "Default")
      (node (ref "K3") (pin "O1") (pinfunction "O_O1") (pintype "passive"))
      (node (ref "X3") (pin "1") (pinfunction "KL_1") (pintype "passive"))
    )
    (net (code "56") (name "Net-(K3B-P)") (class "Default")
      (node (ref "K3") (pin "P1") (pinfunction "P_P1") (pintype "passive"))
      (node (ref "X3") (pin "2") (pinfunction "KL_2") (pintype "passive"))
    )
    (net (code "57") (name "Net-(K3B-S)") (class "Default")
      (node (ref "K3") (pin "S1") (pinfunction "S_S1") (pintype "passive"))
      (node (ref "X3") (pin "3") (pinfunction "KL_3") (pintype "passive"))
    )
    (net (code "58") (name "Net-(K3C-O)") (class "Default")
      (node (ref "K3") (pin "O2") (pinfunction "O_O2") (pintype "passive"))
      (node (ref "X3") (pin "4") (pinfunction "KL_4") (pintype "passive"))
    )
    (net (code "59") (name "Net-(K3C-P)") (class "Default")
      (node (ref "K3") (pin "P2") (pinfunction "P_P2") (pintype "passive"))
      (node (ref "X3") (pin "5") (pinfunction "KL_5") (pintype "passive"))
    )
    (net (code "60") (name "Net-(K3C-S)") (class "Default")
      (node (ref "K3") (pin "S2") (pinfunction "S_S2") (pintype "passive"))
      (node (ref "X3") (pin "6") (pinfunction "KL_6") (pintype "passive"))
    )
    (net (code "61") (name "Net-(LED1-PadA)") (class "Default")
      (node (ref "LED1") (pin "A") (pinfunction "A_A") (pintype "passive"))
      (node (ref "R10") (pin "1") (pinfunction "1_1") (pintype "passive"))
    )
    (net (code "62") (name "Net-(LED2-PadA)") (class "Default")
      (node (ref "LED2") (pin "A") (pinfunction "A_A") (pintype "passive"))
      (node (ref "R11") (pin "1") (pinfunction "1_1") (pintype "passive"))
    )
    (net (code "63") (name "Net-(LED3-PadA)") (class "Default")
      (node (ref "LED3") (pin "A") (pinfunction "A_A") (pintype "passive"))
      (node (ref "R12") (pin "1") (pinfunction "1_1") (pintype "passive"))
    )
    (net (code "64") (name "Net-(LED4-PadA)") (class "Default")
      (node (ref "LED4") (pin "A") (pinfunction "A_A") (pintype "passive"))
      (node (ref "R16") (pin "1") (pinfunction "1_1") (pintype "passive"))
    )
    (net (code "65") (name "Net-(LED5-PadA)") (class "Default")
      (node (ref "LED5") (pin "A") (pinfunction "A_A") (pintype "passive"))
      (node (ref "R17") (pin "1") (pinfunction "1_1") (pintype "passive"))
    )
    (net (code "66") (name "Net-(LED6-PadA)") (class "Default")
      (node (ref "LED6") (pin "A") (pinfunction "A_A") (pintype "passive"))
      (node (ref "R18") (pin "1") (pinfunction "1_1") (pintype "passive"))
    )
    (net (code "67") (name "Net-(LED7-PadA)") (class "Default")
      (node (ref "LED7") (pin "A") (pinfunction "A_A") (pintype "passive"))
      (node (ref "R19") (pin "1") (pinfunction "1_1") (pintype "passive"))
    )
    (net (code "68") (name "Net-(LED8-PadA)") (class "Default")
      (node (ref "LED8") (pin "A") (pinfunction "A_A") (pintype "passive"))
      (node (ref "R21") (pin "1") (pinfunction "1_1") (pintype "passive"))
    )
    (net (code "69") (name "Net-(LED9-PadA)") (class "Default")
      (node (ref "LED9") (pin "A") (pinfunction "A_A") (pintype "passive"))
      (node (ref "R9") (pin "1") (pinfunction "1_1") (pintype "passive"))
    )
    (net (code "70") (name "Net-(LED10-PadA)") (class "Default")
      (node (ref "LED10") (pin "A") (pinfunction "A_A") (pintype "passive"))
      (node (ref "R8") (pin "1") (pinfunction "1_1") (pintype "passive"))
    )
    (net (code "71") (name "Net-(LED11-PadA)") (class "Default")
      (node (ref "LED11") (pin "A") (pinfunction "A_A") (pintype "passive"))
      (node (ref "R7") (pin "1") (pinfunction "1_1") (pintype "passive"))
    )
    (net (code "72") (name "Net-(LED12-PadA)") (class "Default")
      (node (ref "LED12") (pin "A") (pinfunction "A_A") (pintype "passive"))
      (node (ref "R6") (pin "1") (pinfunction "1_1") (pintype "passive"))
    )
    (net (code "73") (name "Net-(LED13-PadA)") (class "Default")
      (node (ref "LED13") (pin "A") (pinfunction "A_A") (pintype "passive"))
      (node (ref "R5") (pin "1") (pinfunction "1_1") (pintype "passive"))
    )
    (net (code "74") (name "Net-(LED14-PadA)") (class "Default")
      (node (ref "LED14") (pin "A") (pinfunction "A_A") (pintype "passive"))
      (node (ref "R4") (pin "1") (pinfunction "1_1") (pintype "passive"))
    )
    (net (code "75") (name "Net-(LED15-PadA)") (class "Default")
      (node (ref "LED15") (pin "A") (pinfunction "A_A") (pintype "passive"))
      (node (ref "R3") (pin "1") (pinfunction "1_1") (pintype "passive"))
    )
    (net (code "76") (name "Net-(LED16-PadA)") (class "Default")
      (node (ref "LED16") (pin "A") (pinfunction "A_A") (pintype "passive"))
      (node (ref "R2") (pin "1") (pinfunction "1_1") (pintype "passive"))
    )
    (net (code "77") (name "Net-(LED17-PadA)") (class "Default")
      (node (ref "LED17") (pin "A") (pinfunction "A_A") (pintype "passive"))
      (node (ref "R20") (pin "1") (pinfunction "1_1") (pintype "passive"))
    )
    (net (code "78") (name "Net-(LED18-PadA)") (class "Default")
      (node (ref "LED18") (pin "A") (pinfunction "A_A") (pintype "passive"))
      (node (ref "R1") (pin "1") (pinfunction "1_1") (pintype "passive"))
    )
    (net (code "79") (name "Net-(OK1-C)") (class "Default")
      (node (ref "OK1") (pin "2") (pinfunction "C_2") (pintype "passive"))
      (node (ref "R23") (pin "2") (pinfunction "2_2") (pintype "passive"))
    )
    (net (code "80") (name "Net-(OK2-C)") (class "Default")
      (node (ref "OK2") (pin "2") (pinfunction "C_2") (pintype "passive"))
      (node (ref "R43") (pin "2") (pinfunction "2_2") (pintype "passive"))
    )
    (net (code "81") (name "Net-(OK2-COL)") (class "Default")
      (node (ref "OK2") (pin "4") (pinfunction "COL_4") (pintype "passive"))
      (node (ref "X4") (pin "4") (pinfunction "KL_4") (pintype "passive"))
    )
    (net (code "82") (name "Net-(OK2-EMIT)") (class "Default")
      (node (ref "OK2") (pin "3") (pinfunction "EMIT_3") (pintype "passive"))
      (node (ref "X4") (pin "3") (pinfunction "KL_3") (pintype "passive"))
    )
    (net (code "83") (name "Net-(R34-S)") (class "Default")
      (node (ref "R33") (pin "2") (pinfunction "2_2") (pintype "passive"))
      (node (ref "R34") (pin "2") (pinfunction "S_2") (pintype "passive"))
    )
    (net (code "84") (name "Net-(T1-B)") (class "Default")
      (node (ref "R13") (pin "2") (pinfunction "2_2") (pintype "passive"))
      (node (ref "T1") (pin "2") (pinfunction "B_2") (pintype "passive"))
    )
    (net (code "85") (name "Net-(T1-C)") (class "Default")
      (node (ref "D2") (pin "A") (pinfunction "A_A") (pintype "passive"))
      (node (ref "K1") (pin "2") (pinfunction "2_2") (pintype "passive"))
      (node (ref "T1") (pin "3") (pinfunction "C_3") (pintype "passive"))
    )
    (net (code "86") (name "Net-(T2-B)") (class "Default")
      (node (ref "R14") (pin "2") (pinfunction "2_2") (pintype "passive"))
      (node (ref "T2") (pin "2") (pinfunction "B_2") (pintype "passive"))
    )
    (net (code "87") (name "Net-(T2-C)") (class "Default")
      (node (ref "D3") (pin "A") (pinfunction "A_A") (pintype "passive"))
      (node (ref "K2") (pin "1") (pinfunction "1_1") (pintype "passive"))
      (node (ref "T2") (pin "3") (pinfunction "C_3") (pintype "passive"))
    )
    (net (code "88") (name "Net-(T3-B)") (class "Default")
      (node (ref "R15") (pin "2") (pinfunction "2_2") (pintype "passive"))
      (node (ref "T3") (pin "2") (pinfunction "B_2") (pintype "passive"))
    )
    (net (code "89") (name "Net-(T3-C)") (class "Default")
      (node (ref "D4") (pin "A") (pinfunction "A_A") (pintype "passive"))
      (node (ref "K3") (pin "1") (pinfunction "1_1") (pintype "passive"))
      (node (ref "T3") (pin "3") (pinfunction "C_3") (pintype "passive"))
    )
    (net (code "90") (name "P808") (class "Default")
      (node (ref "IC2") (pin "6") (pinfunction "O_6") (pintype "output"))
      (node (ref "U$1") (pin "8") (pinfunction "TIMER7_8") (pintype "passive"))
    )
    (net (code "91") (name "P809") (class "Default")
      (node (ref "IC3") (pin "10") (pinfunction "O_10") (pintype "output"))
      (node (ref "U$1") (pin "9") (pinfunction "TIMER5_9") (pintype "passive"))
    )
    (net (code "92") (name "P810") (class "Default")
      (node (ref "IC3") (pin "8") (pinfunction "O_8") (pintype "output"))
      (node (ref "U$1") (pin "10") (pinfunction "TIMER6_10") (pintype "passive"))
    )
    (net (code "93") (name "P813") (class "Default")
      (node (ref "IC5") (pin "8") (pinfunction "A4_8") (pintype "input"))
      (node (ref "U$1") (pin "13") (pinfunction "EHRPWM2B_13") (pintype "passive"))
    )
    (net (code "94") (name "P814") (class "Default")
      (node (ref "IC2") (pin "4") (pinfunction "O_4") (pintype "output"))
      (node (ref "U$1") (pin "14") (pinfunction "GPIO0_26_14") (pintype "passive"))
    )
    (net (code "95") (name "P815") (class "Default")
      (node (ref "IC5") (pin "13") (pinfunction "A2_13") (pintype "input"))
      (node (ref "U$1") (pin "15") (pinfunction "GPIO1_15_15") (pintype "passive"))
    )
    (net (code "96") (name "P817") (class "Default")
      (node (ref "IC2") (pin "2") (pinfunction "O_2") (pintype "output"))
      (node (ref "U$1") (pin "17") (pinfunction "GPIO0_27_17") (pintype "passive"))
    )
    (net (code "97") (name "P818") (class "Default")
      (node (ref "IC6") (pin "6") (pinfunction "O_6") (pintype "output"))
      (node (ref "U$1") (pin "18") (pinfunction "GPIO2_1_18") (pintype "passive"))
    )
    (net (code "98") (name "P819") (class "Default")
      (node (ref "IC5") (pin "11") (pinfunction "A1_11") (pintype "input"))
      (node (ref "U$1") (pin "19") (pinfunction "EHRPWM2A_19") (pintype "passive"))
    )
    (net (code "99") (name "P914") (class "Default")
      (node (ref "IC5") (pin "15") (pinfunction "A3_15") (pintype "input"))
      (node (ref "U$1") (pin "60") (pinfunction "EHRPWM1A_60") (pintype "passive"))
    )
    (net (code "100") (name "P920") (class "Default")
      (node (ref "IC5") (pin "6") (pinfunction "A3_6") (pintype "input"))
      (node (ref "U$1") (pin "66") (pinfunction "I2C2_SDA_66") (pintype "passive"))
    )
    (net (code "101") (name "P922") (class "Default")
      (node (ref "IC5") (pin "17") (pinfunction "A4_17") (pintype "input"))
      (node (ref "U$1") (pin "68") (pinfunction "UART2_RXD_68") (pintype "passive"))
    )
    (net (code "102") (name "P924") (class "Default")
      (node (ref "IC5") (pin "4") (pinfunction "A2_4") (pintype "input"))
      (node (ref "U$1") (pin "70") (pinfunction "UART1_TXD_70") (pintype "passive"))
    )
    (net (code "103") (name "P926") (class "Default")
      (node (ref "IC5") (pin "2") (pinfunction "A1_2") (pintype "input"))
      (node (ref "U$1") (pin "72") (pinfunction "UART1_RXD_72") (pintype "passive"))
    )
    (net (code "104") (name "PWM0B_3V") (class "Default")
      (node (ref "IC4") (pin "2") (pinfunction "A1_2") (pintype "input"))
      (node (ref "U$1") (pin "75") (pinfunction "SPI1_DO_75") (pintype "passive"))
    )
    (net (code "105") (name "PWM0_5V") (class "Default")
      (node (ref "IC4") (pin "5") (pinfunction "Y3_5") (pintype "tri_state"))
      (node (ref "R23") (pin "1") (pinfunction "1_1") (pintype "passive"))
      (node (ref "R36") (pin "1") (pinfunction "1_1") (pintype "passive"))
    )
    (net (code "106") (name "PWM1B_3V") (class "Default")
      (node (ref "IC4") (pin "13") (pinfunction "A2_13") (pintype "input"))
      (node (ref "U$1") (pin "62") (pinfunction "EHRPWM1B_62") (pintype "passive"))
    )
    (net (code "107") (name "RELAY1_5V") (class "Default")
      (node (ref "IC4") (pin "12") (pinfunction "Y4_12") (pintype "tri_state"))
      (node (ref "R13") (pin "1") (pinfunction "1_1") (pintype "passive"))
      (node (ref "R39") (pin "1") (pinfunction "1_1") (pintype "passive"))
    )
    (net (code "108") (name "RELAY2_5V") (class "Default")
      (node (ref "IC4") (pin "7") (pinfunction "Y2_7") (pintype "tri_state"))
      (node (ref "R14") (pin "1") (pinfunction "1_1") (pintype "passive"))
      (node (ref "R37") (pin "1") (pinfunction "1_1") (pintype "passive"))
    )
    (net (code "109") (name "RELAY3_5V") (class "Default")
      (node (ref "IC4") (pin "9") (pinfunction "Y1_9") (pintype "tri_state"))
      (node (ref "R15") (pin "1") (pinfunction "1_1") (pintype "passive"))
      (node (ref "R38") (pin "1") (pinfunction "1_1") (pintype "passive"))
    )
    (net (code "110") (name "SW1_3V") (class "Default")
      (node (ref "IC6") (pin "4") (pinfunction "O_4") (pintype "output"))
      (node (ref "U$1") (pin "26") (pinfunction "GPIO1_29_26") (pintype "passive"))
    )
    (net (code "111") (name "SW1_5V") (class "Default")
      (node (ref "IC6") (pin "3") (pinfunction "I_3") (pintype "input"))
      (node (ref "J18") (pin "2") (pinfunction "S_2") (pintype "passive"))
      (node (ref "LED14") (pin "K") (pinfunction "C_K") (pintype "passive"))
    )
    (net (code "112") (name "SW2_3V") (class "Default")
      (node (ref "IC6") (pin "2") (pinfunction "O_2") (pintype "output"))
      (node (ref "U$1") (pin "58") (pinfunction "GPIO1_28_58") (pintype "passive"))
    )
    (net (code "113") (name "SW2_5V") (class "Default")
      (node (ref "IC6") (pin "1") (pinfunction "I_1") (pintype "input"))
      (node (ref "J19") (pin "2") (pinfunction "S_2") (pintype "passive"))
      (node (ref "LED15") (pin "K") (pinfunction "C_K") (pintype "passive"))
    )
    (net (code "114") (name "SW3_3V") (class "Default")
      (node (ref "IC3") (pin "6") (pinfunction "O_6") (pintype "output"))
      (node (ref "U$1") (pin "71") (pinfunction "GPIO3_21_71") (pintype "passive"))
    )
    (net (code "115") (name "SW3_5V") (class "Default")
      (node (ref "IC3") (pin "5") (pinfunction "I_5") (pintype "input"))
      (node (ref "J20") (pin "2") (pinfunction "S_2") (pintype "passive"))
      (node (ref "LED16") (pin "K") (pinfunction "C_K") (pintype "passive"))
    )
    (net (code "116") (name "SW4_3V") (class "Default")
      (node (ref "IC3") (pin "4") (pinfunction "O_4") (pintype "output"))
      (node (ref "U$1") (pin "77") (pinfunction "SPI1_SCLK_77") (pintype "passive"))
    )
    (net (code "117") (name "SW4_5V") (class "Default")
      (node (ref "IC3") (pin "3") (pinfunction "I_3") (pintype "input"))
      (node (ref "J21") (pin "2") (pinfunction "S_2") (pintype "passive"))
      (node (ref "LED17") (pin "K") (pinfunction "C_K") (pintype "passive"))
    )
    (net (code "118") (name "SYS_5V") (class "Default")
      (node (ref "U$1") (pin "53") (pinfunction "SYS_5V_53") (pintype "power_in"))
    )
    (net (code "119") (name "VDD_3V3EXP") (class "Default")
      (node (ref "C5") (pin "1") (pinfunction "1_1") (pintype "passive"))
      (node (ref "C6") (pin "1") (pinfunction "1_1") (pintype "passive"))
      (node (ref "C7") (pin "1") (pinfunction "1_1") (pintype "passive"))
      (node (ref "IC2") (pin "14") (pinfunction "VCC_14") (pintype "power_in"))
      (node (ref "IC3") (pin "14") (pinfunction "VCC_14") (pintype "power_in"))
      (node (ref "IC6") (pin "14") (pinfunction "VCC_14") (pintype "power_in"))
      (node (ref "U$1") (pin "49") (pinfunction "VDD_3V3EXP_49") (pintype "power_in"))
      (node (ref "U$1") (pin "50") (pinfunction "VDD_3V3EXP_50") (pintype "power_in"))
    )
    (net (code "120") (name "VDD_5V") (class "Default")
      (node (ref "C2") (pin "+") (pinfunction "+_+") (pintype "passive"))
      (node (ref "C8") (pin "1") (pinfunction "1_1") (pintype "passive"))
      (node (ref "C9") (pin "1") (pinfunction "1_1") (pintype "passive"))
      (node (ref "D2") (pin "C") (pinfunction "C_C") (pintype "passive"))
      (node (ref "D3") (pin "C") (pinfunction "C_C") (pintype "passive"))
      (node (ref "D4") (pin "C") (pinfunction "C_C") (pintype "passive"))
      (node (ref "DC1") (pin "2") (pinfunction "+VIN_2") (pintype "passive"))
      (node (ref "IC1") (pin "4") (pinfunction "FB_4") (pintype "input"))
      (node (ref "IC4") (pin "20") (pinfunction "VCC_20") (pintype "power_in"))
      (node (ref "IC5") (pin "20") (pinfunction "VCC_20") (pintype "power_in"))
      (node (ref "J10") (pin "1") (pinfunction "S_1") (pintype "passive"))
      (node (ref "J11") (pin "1") (pinfunction "S_1") (pintype "passive"))
      (node (ref "J12") (pin "1") (pinfunction "S_1") (pintype "passive"))
      (node (ref "J13") (pin "1") (pinfunction "S_1") (pintype "passive"))
      (node (ref "J14") (pin "1") (pinfunction "S_1") (pintype "passive"))
      (node (ref "J15") (pin "1") (pinfunction "S_1") (pintype "passive"))
      (node (ref "J16") (pin "1") (pinfunction "S_1") (pintype "passive"))
      (node (ref "J17") (pin "1") (pinfunction "S_1") (pintype "passive"))
      (node (ref "J18") (pin "1") (pinfunction "S_1") (pintype "passive"))
      (node (ref "J19") (pin "1") (pinfunction "S_1") (pintype "passive"))
      (node (ref "J20") (pin "1") (pinfunction "S_1") (pintype "passive"))
      (node (ref "J21") (pin "1") (pinfunction "S_1") (pintype "passive"))
      (node (ref "J6") (pin "1") (pinfunction "S_1") (pintype "passive"))
      (node (ref "J7") (pin "1") (pinfunction "S_1") (pintype "passive"))
      (node (ref "J8") (pin "1") (pinfunction "S_1") (pintype "passive"))
      (node (ref "J9") (pin "1") (pinfunction "S_1") (pintype "passive"))
      (node (ref "K1") (pin "1") (pinfunction "1_1") (pintype "passive"))
      (node (ref "K2") (pin "2") (pinfunction "2_2") (pintype "passive"))
      (node (ref "K3") (pin "2") (pinfunction "2_2") (pintype "passive"))
      (node (ref "L1") (pin "P$2") (pinfunction "2_P$2") (pintype "passive"))
      (node (ref "OK1") (pin "1") (pinfunction "A_1") (pintype "passive"))
      (node (ref "OK2") (pin "1") (pinfunction "A_1") (pintype "passive"))
      (node (ref "R1") (pin "2") (pinfunction "2_2") (pintype "passive"))
      (node (ref "R10") (pin "2") (pinfunction "2_2") (pintype "passive"))
      (node (ref "R11") (pin "2") (pinfunction "2_2") (pintype "passive"))
      (node (ref "R12") (pin "2") (pinfunction "2_2") (pintype "passive"))
      (node (ref "R16") (pin "2") (pinfunction "2_2") (pintype "passive"))
      (node (ref "R17") (pin "2") (pinfunction "2_2") (pintype "passive"))
      (node (ref "R18") (pin "2") (pinfunction "2_2") (pintype "passive"))
      (node (ref "R19") (pin "2") (pinfunction "2_2") (pintype "passive"))
      (node (ref "R2") (pin "2") (pinfunction "2_2") (pintype "passive"))
      (node (ref "R20") (pin "2") (pinfunction "2_2") (pintype "passive"))
      (node (ref "R21") (pin "2") (pinfunction "2_2") (pintype "passive"))
      (node (ref "R24") (pin "2") (pinfunction "2_2") (pintype "passive"))
      (node (ref "R25") (pin "2") (pinfunction "2_2") (pintype "passive"))
      (node (ref "R3") (pin "2") (pinfunction "2_2") (pintype "passive"))
      (node (ref "R4") (pin "2") (pinfunction "2_2") (pintype "passive"))
      (node (ref "R5") (pin "2") (pinfunction "2_2") (pintype "passive"))
      (node (ref "R6") (pin "2") (pinfunction "2_2") (pintype "passive"))
      (node (ref "R7") (pin "2") (pinfunction "2_2") (pintype "passive"))
      (node (ref "R8") (pin "2") (pinfunction "2_2") (pintype "passive"))
      (node (ref "R9") (pin "2") (pinfunction "2_2") (pintype "passive"))
      (node (ref "U$1") (pin "51") (pinfunction "VDD_5V_51") (pintype "power_in"))
      (node (ref "U$1") (pin "52") (pinfunction "VDD_5V_52") (pintype "power_in"))
    )
    (net (code "121") (name "X_DIR_3V") (class "Default")
      (node (ref "IC4") (pin "15") (pinfunction "A3_15") (pintype "input"))
      (node (ref "U$1") (pin "65") (pinfunction "I2C2_SCL_65") (pintype "passive"))
    )
    (net (code "122") (name "X_DIR_5V") (class "Default")
      (node (ref "IC5") (pin "16") (pinfunction "Y2_16") (pintype "tri_state"))
      (node (ref "J1") (pin "2") (pinfunction "S_2") (pintype "passive"))
      (node (ref "RN1") (pin "7") (pinfunction "7_7") (pintype "passive"))
    )
    (net (code "123") (name "X_STEP_5V") (class "Default")
      (node (ref "IC5") (pin "5") (pinfunction "Y3_5") (pintype "tri_state"))
      (node (ref "J1") (pin "3") (pinfunction "S_3") (pintype "passive"))
      (node (ref "RN1") (pin "6") (pinfunction "6_6") (pintype "passive"))
    )
    (net (code "124") (name "Y_DIR_3V") (class "Default")
      (node (ref "IC4") (pin "8") (pinfunction "A4_8") (pintype "input"))
      (node (ref "U$1") (pin "57") (pinfunction "UART4_RXD_57") (pintype "passive"))
    )
    (net (code "125") (name "Y_DIR_5V") (class "Default")
      (node (ref "IC5") (pin "14") (pinfunction "Y3_14") (pintype "tri_state"))
      (node (ref "J2") (pin "2") (pinfunction "S_2") (pintype "passive"))
      (node (ref "RN1") (pin "5") (pinfunction "5_5") (pintype "passive"))
    )
    (net (code "126") (name "Y_STEP_3V") (class "Default")
      (node (ref "IC4") (pin "6") (pinfunction "A3_6") (pintype "input"))
      (node (ref "U$1") (pin "59") (pinfunction "UART4_TXD_59") (pintype "passive"))
    )
    (net (code "127") (name "Y_STEP_5V") (class "Default")
      (node (ref "IC5") (pin "7") (pinfunction "Y2_7") (pintype "tri_state"))
      (node (ref "J2") (pin "3") (pinfunction "S_3") (pintype "passive"))
      (node (ref "RN1") (pin "4") (pinfunction "4_4") (pintype "passive"))
    )
    (net (code "128") (name "Z_DIR_3V") (class "Default")
      (node (ref "IC4") (pin "17") (pinfunction "A4_17") (pintype "input"))
      (node (ref "U$1") (pin "69") (pinfunction "GPIO1_17_69") (pintype "passive"))
    )
    (net (code "129") (name "Z_DIR_5V") (class "Default")
      (node (ref "IC5") (pin "12") (pinfunction "Y4_12") (pintype "tri_state"))
      (node (ref "J3") (pin "2") (pinfunction "S_2") (pintype "passive"))
      (node (ref "RN1") (pin "3") (pinfunction "3_3") (pintype "passive"))
    )
    (net (code "130") (name "Z_STEP_3V") (class "Default")
      (node (ref "IC4") (pin "4") (pinfunction "A2_4") (pintype "input"))
      (node (ref "U$1") (pin "67") (pinfunction "UART2_TXD_67") (pintype "passive"))
    )
    (net (code "131") (name "Z_STEP_5V") (class "Default")
      (node (ref "IC5") (pin "9") (pinfunction "Y1_9") (pintype "tri_state"))
      (node (ref "J3") (pin "3") (pinfunction "S_3") (pintype "passive"))
      (node (ref "RN1") (pin "2") (pinfunction "2_2") (pintype "passive"))
    )
    (net (code "132") (name "unconnected-(IC3A-O-Pad12)") (class "Default")
      (node (ref "IC3") (pin "12") (pinfunction "O_12") (pintype "output"))
    )
    (net (code "133") (name "unconnected-(U$1-AIN1-Pad86)") (class "Default")
      (node (ref "U$1") (pin "86") (pinfunction "AIN1_86") (pintype "passive"))
    )
    (net (code "134") (name "unconnected-(U$1-AIN2-Pad83)") (class "Default")
      (node (ref "U$1") (pin "83") (pinfunction "AIN2_83") (pintype "passive"))
    )
    (net (code "135") (name "unconnected-(U$1-AIN3-Pad84)") (class "Default")
      (node (ref "U$1") (pin "84") (pinfunction "AIN3_84") (pintype "passive"))
    )
    (net (code "136") (name "unconnected-(U$1-AIN4-Pad79)") (class "Default")
      (node (ref "U$1") (pin "79") (pinfunction "AIN4_79") (pintype "passive"))
    )
    (net (code "137") (name "unconnected-(U$1-AIN5-Pad82)") (class "Default")
      (node (ref "U$1") (pin "82") (pinfunction "AIN5_82") (pintype "passive"))
    )
    (net (code "138") (name "unconnected-(U$1-AIN6-Pad81)") (class "Default")
      (node (ref "U$1") (pin "81") (pinfunction "AIN6_81") (pintype "passive"))
    )
    (net (code "139") (name "unconnected-(U$1-GNDA_ADC-Pad80)") (class "Default")
      (node (ref "U$1") (pin "80") (pinfunction "GNDA_ADC_80") (pintype "passive"))
    )
    (net (code "140") (name "unconnected-(U$1-GPIO1_0-Pad25)") (class "Default")
      (node (ref "U$1") (pin "25") (pinfunction "GPIO1_0_25") (pintype "passive"))
    )
    (net (code "141") (name "unconnected-(U$1-GPIO1_1-Pad24)") (class "Default")
      (node (ref "U$1") (pin "24") (pinfunction "GPIO1_1_24") (pintype "passive"))
    )
    (net (code "142") (name "unconnected-(U$1-GPIO1_2-Pad5)") (class "Default")
      (node (ref "U$1") (pin "5") (pinfunction "GPIO1_2_5") (pintype "passive"))
    )
    (net (code "143") (name "unconnected-(U$1-GPIO1_3-Pad6)") (class "Default")
      (node (ref "U$1") (pin "6") (pinfunction "GPIO1_3_6") (pintype "passive"))
    )
    (net (code "144") (name "unconnected-(U$1-GPIO1_4-Pad23)") (class "Default")
      (node (ref "U$1") (pin "23") (pinfunction "GPIO1_4_23") (pintype "passive"))
    )
    (net (code "145") (name "unconnected-(U$1-GPIO1_5-Pad22)") (class "Default")
      (node (ref "U$1") (pin "22") (pinfunction "GPIO1_5_22") (pintype "passive"))
    )
    (net (code "146") (name "unconnected-(U$1-GPIO1_6-Pad3)") (class "Default")
      (node (ref "U$1") (pin "3") (pinfunction "GPIO1_6_3") (pintype "passive"))
    )
    (net (code "147") (name "unconnected-(U$1-GPIO1_7-Pad4)") (class "Default")
      (node (ref "U$1") (pin "4") (pinfunction "GPIO1_7_4") (pintype "passive"))
    )
    (net (code "148") (name "unconnected-(U$1-GPIO1_30-Pad21)") (class "Default")
      (node (ref "U$1") (pin "21") (pinfunction "GPIO1_30_21") (pintype "passive"))
    )
    (net (code "149") (name "unconnected-(U$1-GPIO1_31-Pad20)") (class "Default")
      (node (ref "U$1") (pin "20") (pinfunction "GPIO1_31_20") (pintype "passive"))
    )
    (net (code "150") (name "unconnected-(U$1-GPIO2_6-Pad45)") (class "Default")
      (node (ref "U$1") (pin "45") (pinfunction "GPIO2_6_45") (pintype "passive"))
    )
    (net (code "151") (name "unconnected-(U$1-GPIO2_7-Pad46)") (class "Default")
      (node (ref "U$1") (pin "46") (pinfunction "GPIO2_7_46") (pintype "passive"))
    )
    (net (code "152") (name "unconnected-(U$1-GPIO2_8-Pad43)") (class "Default")
      (node (ref "U$1") (pin "43") (pinfunction "GPIO2_8_43") (pintype "passive"))
    )
    (net (code "153") (name "unconnected-(U$1-GPIO2_9-Pad44)") (class "Default")
      (node (ref "U$1") (pin "44") (pinfunction "GPIO2_9_44") (pintype "passive"))
    )
    (net (code "154") (name "unconnected-(U$1-GPIO2_10-Pad41)") (class "Default")
      (node (ref "U$1") (pin "41") (pinfunction "GPIO2_10_41") (pintype "passive"))
    )
    (net (code "155") (name "unconnected-(U$1-GPIO2_11-Pad42)") (class "Default")
      (node (ref "U$1") (pin "42") (pinfunction "GPIO2_11_42") (pintype "passive"))
    )
    (net (code "156") (name "unconnected-(U$1-GPIO2_12-Pad39)") (class "Default")
      (node (ref "U$1") (pin "39") (pinfunction "GPIO2_12_39") (pintype "passive"))
    )
    (net (code "157") (name "unconnected-(U$1-GPIO2_13-Pad40)") (class "Default")
      (node (ref "U$1") (pin "40") (pinfunction "GPIO2_13_40") (pintype "passive"))
    )
    (net (code "158") (name "unconnected-(U$1-GPIO2_22-Pad27)") (class "Default")
      (node (ref "U$1") (pin "27") (pinfunction "GPIO2_22_27") (pintype "passive"))
    )
    (net (code "159") (name "unconnected-(U$1-GPIO2_23-Pad29)") (class "Default")
      (node (ref "U$1") (pin "29") (pinfunction "GPIO2_23_29") (pintype "passive"))
    )
    (net (code "160") (name "unconnected-(U$1-GPIO2_24-Pad28)") (class "Default")
      (node (ref "U$1") (pin "28") (pinfunction "GPIO2_24_28") (pintype "passive"))
    )
    (net (code "161") (name "unconnected-(U$1-GPIO2_25-Pad30)") (class "Default")
      (node (ref "U$1") (pin "30") (pinfunction "GPIO2_25_30") (pintype "passive"))
    )
    (net (code "162") (name "unconnected-(U$1-I2C1_SCL-Pad63)") (class "Default")
      (node (ref "U$1") (pin "63") (pinfunction "I2C1_SCL_63") (pintype "passive"))
    )
    (net (code "163") (name "unconnected-(U$1-I2C1_SDA-Pad64)") (class "Default")
      (node (ref "U$1") (pin "64") (pinfunction "I2C1_SDA_64") (pintype "passive"))
    )
    (net (code "164") (name "unconnected-(U$1-PWR_BUT-Pad55)") (class "Default")
      (node (ref "U$1") (pin "55") (pinfunction "PWR_BUT_55") (pintype "passive"))
    )
    (net (code "165") (name "unconnected-(U$1-SYS_5V-Pad54)") (class "Default")
      (node (ref "U$1") (pin "54") (pinfunction "SYS_5V_54") (pintype "passive"))
    )
    (net (code "166") (name "unconnected-(U$1-SYS_RESETN-Pad56)") (class "Default")
      (node (ref "U$1") (pin "56") (pinfunction "SYS_RESETN_56") (pintype "passive"))
    )
    (net (code "167") (name "unconnected-(U$1-UART3_CTSN-Pad36)") (class "Default")
      (node (ref "U$1") (pin "36") (pinfunction "UART3_CTSN_36") (pintype "passive"))
    )
    (net (code "168") (name "unconnected-(U$1-UART3_RTSN-Pad34)") (class "Default")
      (node (ref "U$1") (pin "34") (pinfunction "UART3_RTSN_34") (pintype "passive"))
    )
    (net (code "169") (name "unconnected-(U$1-UART4_CTSN-Pad35)") (class "Default")
      (node (ref "U$1") (pin "35") (pinfunction "UART4_CTSN_35") (pintype "passive"))
    )
    (net (code "170") (name "unconnected-(U$1-UART4_RTSN-Pad33)") (class "Default")
      (node (ref "U$1") (pin "33") (pinfunction "UART4_RTSN_33") (pintype "passive"))
    )
    (net (code "171") (name "unconnected-(U$1-UART5_CTSN-Pad31)") (class "Default")
      (node (ref "U$1") (pin "31") (pinfunction "UART5_CTSN_31") (pintype "passive"))
    )
    (net (code "172") (name "unconnected-(U$1-UART5_RTSN-Pad32)") (class "Default")
      (node (ref "U$1") (pin "32") (pinfunction "UART5_RTSN_32") (pintype "passive"))
    )
    (net (code "173") (name "unconnected-(U$1-UART5_RXD-Pad38)") (class "Default")
      (node (ref "U$1") (pin "38") (pinfunction "UART5_RXD_38") (pintype "passive"))
    )
    (net (code "174") (name "unconnected-(U$1-UART5_TXD-Pad37)") (class "Default")
      (node (ref "U$1") (pin "37") (pinfunction "UART5_TXD_37") (pintype "passive"))
    )
    (net (code "175") (name "unconnected-(U$1-VDD_ADC-Pad78)") (class "Default")
      (node (ref "U$1") (pin "78") (pinfunction "VDD_ADC_78") (pintype "passive"))
    )
    (net (code "176") (name "~{OUTPUT_ENABLE}") (class "Default")
      (node (ref "IC4") (pin "1") (pinfunction "G_1") (pintype "input"))
      (node (ref "IC4") (pin "19") (pinfunction "G_19") (pintype "input"))
      (node (ref "IC5") (pin "1") (pinfunction "G_1") (pintype "input"))
      (node (ref "IC5") (pin "19") (pinfunction "G_19") (pintype "input"))
      (node (ref "Q2") (pin "1") (pinfunction "D_1") (pintype "passive"))
      (node (ref "R25") (pin "1") (pinfunction "1_1") (pintype "passive"))
    )
  )
)
